# hih8000.net
KiCad netlist of a schematic drawn in EAGLE
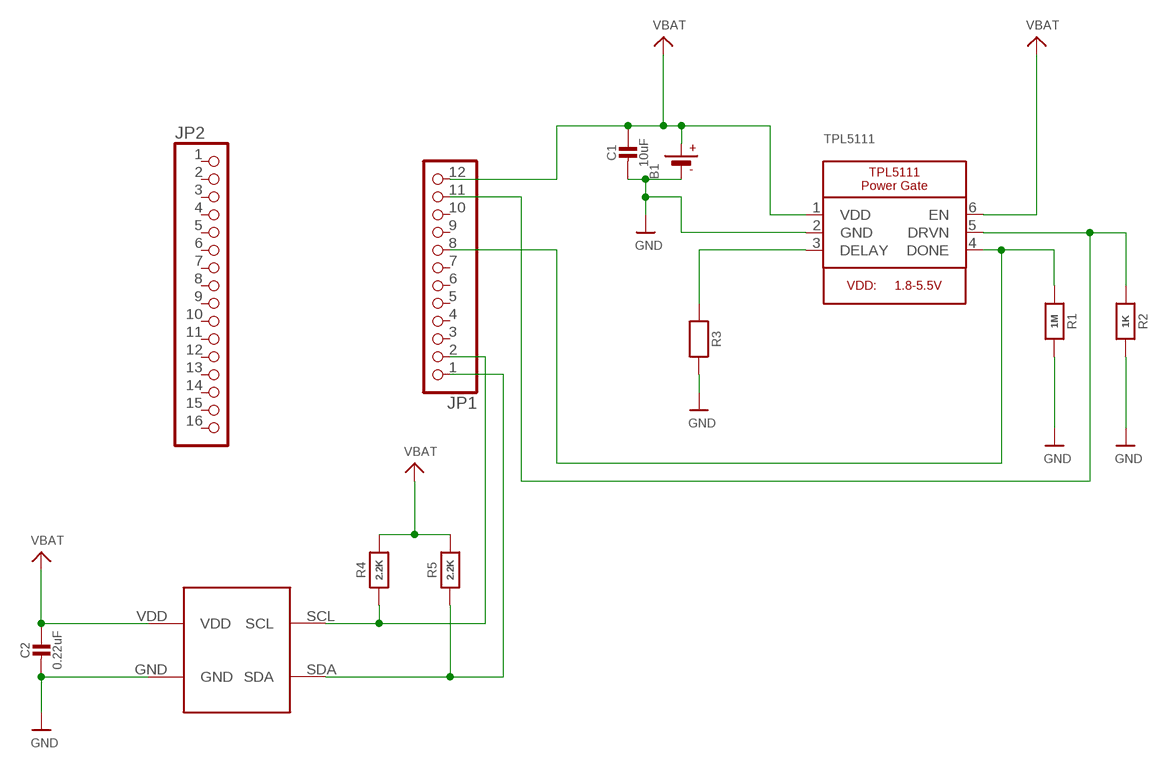
[diagram p0: schematic, sheet 1]

(export (version "E")
  (design (tool "Eeschema 10.0.6"))
  (components
    (comp (ref "B1")
      (value "BATTERY")
      (footprint "eagle-import:JSTPH2")
      (libsource (lib "eagle-import") (part "BATTERY"))
    )
    (comp (ref "C1")
      (value "10uF")
      (footprint "eagle-import:0805-NO")
      (libsource (lib "eagle-import") (part "CAP_CERAMIC0805-NOOUTLINE"))
    )
    (comp (ref "C2")
      (value "0.22uF")
      (footprint "eagle-import:0805-NO")
      (libsource (lib "eagle-import") (part "CAP_CERAMIC0805-NOOUTLINE"))
    )
    (comp (ref "JP1")
      (value "HEADER-1X12")
      (footprint "eagle-import:1X12_ROUND")
      (libsource (lib "eagle-import") (part "HEADER-1X12"))
    )
    (comp (ref "JP2")
      (value "HEADER-1X16ROUND")
      (footprint "eagle-import:1X16_ROUND")
      (libsource (lib "eagle-import") (part "HEADER-1X16ROUND"))
    )
    (comp (ref "R1")
      (value "1M")
      (footprint "eagle-import:0805-NO")
      (libsource (lib "eagle-import") (part "RESISTOR0805_NOOUTLINE"))
    )
    (comp (ref "R2")
      (value "1K")
      (footprint "eagle-import:0805-NO")
      (libsource (lib "eagle-import") (part "RESISTOR0805_NOOUTLINE"))
    )
    (comp (ref "R3")
      (value "RESISTOR0805_NOOUTLINE")
      (footprint "eagle-import:0805-NO")
      (libsource (lib "eagle-import") (part "RESISTOR0805_NOOUTLINE"))
    )
    (comp (ref "R4")
      (value "2.2K")
      (footprint "eagle-import:0805-NO")
      (libsource (lib "eagle-import") (part "RESISTOR0805_NOOUTLINE"))
    )
    (comp (ref "R5")
      (value "2.2K")
      (footprint "eagle-import:0805-NO")
      (libsource (lib "eagle-import") (part "RESISTOR0805_NOOUTLINE"))
    )
    (comp (ref "TPL5111")
      (value "TPL5111")
      (footprint "eagle-import:SOT23-6")
      (libsource (lib "eagle-import") (part "TPL5111"))
    )
    (comp (ref "U$7")
      (value "HIH8000_DEV")
      (footprint "eagle-import:HIH8000")
      (libsource (lib "eagle-import") (part "HIH8000_DEV"))
    )
  )
  (nets
    (net (code "1") (name "GND") (class "Default")
      (node (ref "B1") (pin "1") (pinfunction "-_1") (pintype "passive"))
      (node (ref "C1") (pin "2") (pinfunction "2_2") (pintype "passive"))
      (node (ref "C2") (pin "2") (pinfunction "2_2") (pintype "passive"))
      (node (ref "R1") (pin "2") (pinfunction "2_2") (pintype "passive"))
      (node (ref "R2") (pin "2") (pinfunction "2_2") (pintype "passive"))
      (node (ref "R3") (pin "2") (pinfunction "2_2") (pintype "passive"))
      (node (ref "TPL5111") (pin "2") (pinfunction "GND_2") (pintype "power_in"))
      (node (ref "U$7") (pin "GND") (pinfunction "GND_GND") (pintype "bidirectional"))
    )
    (net (code "2") (name "Net-(JP1-Pad1)") (class "Default")
      (node (ref "JP1") (pin "1") (pinfunction "1_1") (pintype "passive"))
      (node (ref "R5") (pin "1") (pinfunction "1_1") (pintype "passive"))
      (node (ref "U$7") (pin "SDA") (pinfunction "SDA_SDA") (pintype "bidirectional"))
    )
    (net (code "3") (name "Net-(JP1-Pad2)") (class "Default")
      (node (ref "JP1") (pin "2") (pinfunction "2_2") (pintype "passive"))
      (node (ref "R4") (pin "1") (pinfunction "1_1") (pintype "passive"))
      (node (ref "U$7") (pin "SCL") (pinfunction "SCL_SCL") (pintype "bidirectional"))
    )
    (net (code "4") (name "Net-(TPL5111-DELAY)") (class "Default")
      (node (ref "R3") (pin "1") (pinfunction "1_1") (pintype "passive"))
      (node (ref "TPL5111") (pin "3") (pinfunction "DELAY_3") (pintype "input"))
    )
    (net (code "5") (name "Net-(TPL5111-DONE)") (class "Default")
      (node (ref "JP1") (pin "8") (pinfunction "8_8") (pintype "passive"))
      (node (ref "R1") (pin "1") (pinfunction "1_1") (pintype "passive"))
      (node (ref "TPL5111") (pin "4") (pinfunction "DONE_4") (pintype "input"))
    )
    (net (code "6") (name "Net-(TPL5111-DRVN)") (class "Default")
      (node (ref "JP1") (pin "11") (pinfunction "11_11") (pintype "passive"))
      (node (ref "R2") (pin "1") (pinfunction "1_1") (pintype "passive"))
      (node (ref "TPL5111") (pin "5") (pinfunction "DRVN_5") (pintype "output"))
    )
    (net (code "7") (name "VBAT") (class "Default")
      (node (ref "B1") (pin "2") (pinfunction "+_2") (pintype "passive"))
      (node (ref "C1") (pin "1") (pinfunction "1_1") (pintype "passive"))
      (node (ref "C2") (pin "1") (pinfunction "1_1") (pintype "passive"))
      (node (ref "JP1") (pin "12") (pinfunction "12_12") (pintype "passive"))
      (node (ref "R4") (pin "2") (pinfunction "2_2") (pintype "passive"))
      (node (ref "R5") (pin "2") (pinfunction "2_2") (pintype "passive"))
      (node (ref "TPL5111") (pin "1") (pinfunction "VDD_1") (pintype "power_in"))
      (node (ref "TPL5111") (pin "6") (pinfunction "EN_6") (pintype "input"))
      (node (ref "U$7") (pin "VDD") (pinfunction "VDD_VDD") (pintype "bidirectional"))
    )
    (net (code "8") (name "unconnected-(JP1-Pad3)") (class "Default")
      (node (ref "JP1") (pin "3") (pinfunction "3_3") (pintype "passive"))
    )
    (net (code "9") (name "unconnected-(JP1-Pad4)") (class "Default")
      (node (ref "JP1") (pin "4") (pinfunction "4_4") (pintype "passive"))
    )
    (net (code "10") (name "unconnected-(JP1-Pad5)") (class "Default")
      (node (ref "JP1") (pin "5") (pinfunction "5_5") (pintype "passive"))
    )
    (net (code "11") (name "unconnected-(JP1-Pad6)") (class "Default")
      (node (ref "JP1") (pin "6") (pinfunction "6_6") (pintype "passive"))
    )
    (net (code "12") (name "unconnected-(JP1-Pad7)") (class "Default")
      (node (ref "JP1") (pin "7") (pinfunction "7_7") (pintype "passive"))
    )
    (net (code "13") (name "unconnected-(JP1-Pad9)") (class "Default")
      (node (ref "JP1") (pin "9") (pinfunction "9_9") (pintype "passive"))
    )
    (net (code "14") (name "unconnected-(JP1-Pad10)") (class "Default")
      (node (ref "JP1") (pin "10") (pinfunction "10_10") (pintype "passive"))
    )
    (net (code "15") (name "unconnected-(JP2-Pad1)") (class "Default")
      (node (ref "JP2") (pin "1") (pinfunction "1_1") (pintype "passive"))
    )
    (net (code "16") (name "unconnected-(JP2-Pad2)") (class "Default")
      (node (ref "JP2") (pin "2") (pinfunction "2_2") (pintype "passive"))
    )
    (net (code "17") (name "unconnected-(JP2-Pad3)") (class "Default")
      (node (ref "JP2") (pin "3") (pinfunction "3_3") (pintype "passive"))
    )
    (net (code "18") (name "unconnected-(JP2-Pad4)") (class "Default")
      (node (ref "JP2") (pin "4") (pinfunction "4_4") (pintype "passive"))
    )
    (net (code "19") (name "unconnected-(JP2-Pad5)") (class "Default")
      (node (ref "JP2") (pin "5") (pinfunction "5_5") (pintype "passive"))
    )
    (net (code "20") (name "unconnected-(JP2-Pad6)") (class "Default")
      (node (ref "JP2") (pin "6") (pinfunction "6_6") (pintype "passive"))
    )
    (net (code "21") (name "unconnected-(JP2-Pad7)") (class "Default")
      (node (ref "JP2") (pin "7") (pinfunction "7_7") (pintype "passive"))
    )
    (net (code "22") (name "unconnected-(JP2-Pad8)") (class "Default")
      (node (ref "JP2") (pin "8") (pinfunction "8_8") (pintype "passive"))
    )
    (net (code "23") (name "unconnected-(JP2-Pad9)") (class "Default")
      (node (ref "JP2") (pin "9") (pinfunction "9_9") (pintype "passive"))
    )
    (net (code "24") (name "unconnected-(JP2-Pad10)") (class "Default")
      (node (ref "JP2") (pin "10") (pinfunction "10_10") (pintype "passive"))
    )
    (net (code "25") (name "unconnected-(JP2-Pad11)") (class "Default")
      (node (ref "JP2") (pin "11") (pinfunction "11_11") (pintype "passive"))
    )
    (net (code "26") (name "unconnected-(JP2-Pad12)") (class "Default")
      (node (ref "JP2") (pin "12") (pinfunction "12_12") (pintype "passive"))
    )
    (net (code "27") (name "unconnected-(JP2-Pad13)") (class "Default")
      (node (ref "JP2") (pin "13") (pinfunction "13_13") (pintype "passive"))
    )
    (net (code "28") (name "unconnected-(JP2-Pad14)") (class "Default")
      (node (ref "JP2") (pin "14") (pinfunction "14_14") (pintype "passive"))
    )
    (net (code "29") (name "unconnected-(JP2-Pad15)") (class "Default")
      (node (ref "JP2") (pin "15") (pinfunction "15_15") (pintype "passive"))
    )
    (net (code "30") (name "unconnected-(JP2-Pad16)") (class "Default")
      (node (ref "JP2") (pin "16") (pinfunction "16_16") (pintype "passive"))
    )
  )
)
